# RSV.net
KiCad netlist of a schematic drawn in Altium Designer
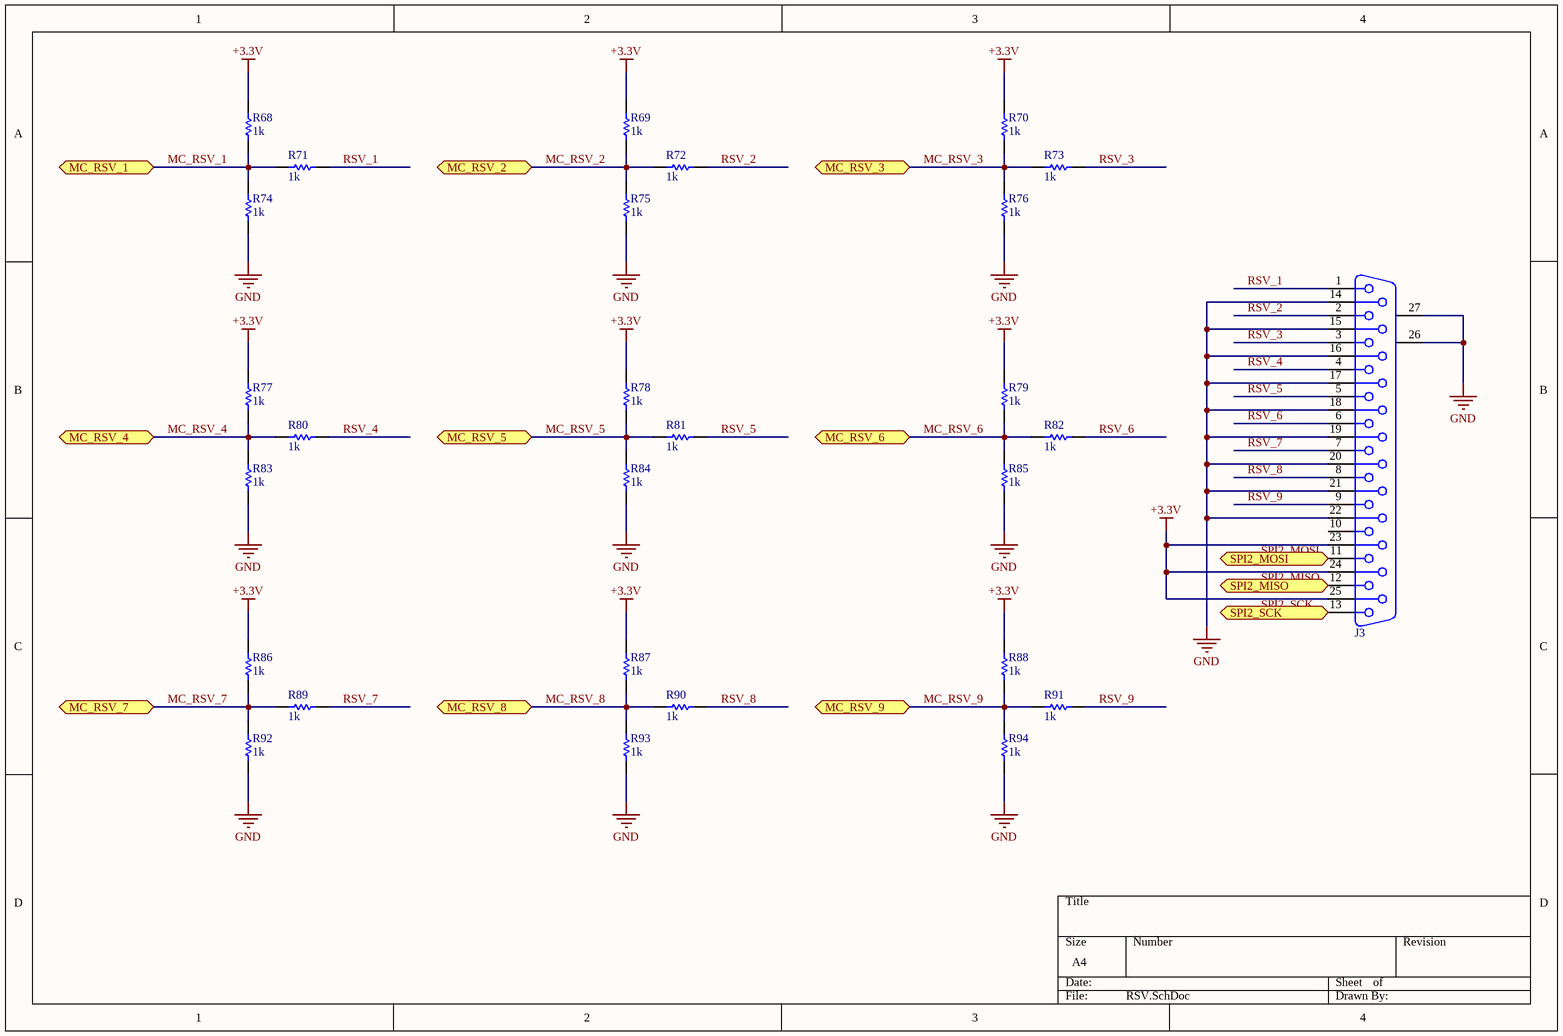
[diagram p0: RSV.SchDoc]

(export (version "E")
  (design (tool "Eeschema 10.0.6"))
  (components
    (comp (ref "J3")
      (value "DB25_Straight")
      (footprint "DB25_Straight")
      (description "Receptacle Assembly, 25 Position, Right Angle")
      (fields (field (name "PUBLISHER") "Altium Limited"))
      (libsource (lib "AfraLIB") (part "DB25_Straight"))
    )
    (comp (ref "R68")
      (value "1k")
      (footprint "R-805")
      (description "Resistor")
      (fields (field (name "Comment") "R-805"))
      (libsource (lib "AfraLIB") (part "R-805"))
    )
    (comp (ref "R69")
      (value "1k")
      (footprint "R-805")
      (description "Resistor")
      (fields (field (name "Comment") "R-805"))
      (libsource (lib "AfraLIB") (part "R-805"))
    )
    (comp (ref "R70")
      (value "1k")
      (footprint "R-805")
      (description "Resistor")
      (fields (field (name "Comment") "R-805"))
      (libsource (lib "AfraLIB") (part "R-805"))
    )
    (comp (ref "R71")
      (value "1k")
      (footprint "R-805")
      (description "Resistor")
      (fields (field (name "Comment") "R-805"))
      (libsource (lib "AfraLIB") (part "R-805"))
    )
    (comp (ref "R72")
      (value "1k")
      (footprint "R-805")
      (description "Resistor")
      (fields (field (name "Comment") "R-805"))
      (libsource (lib "AfraLIB") (part "R-805"))
    )
    (comp (ref "R73")
      (value "1k")
      (footprint "R-805")
      (description "Resistor")
      (fields (field (name "Comment") "R-805"))
      (libsource (lib "AfraLIB") (part "R-805"))
    )
    (comp (ref "R74")
      (value "1k")
      (footprint "R-805")
      (description "Resistor")
      (fields (field (name "Comment") "R-805"))
      (libsource (lib "AfraLIB") (part "R-805"))
    )
    (comp (ref "R75")
      (value "1k")
      (footprint "R-805")
      (description "Resistor")
      (fields (field (name "Comment") "R-805"))
      (libsource (lib "AfraLIB") (part "R-805"))
    )
    (comp (ref "R76")
      (value "1k")
      (footprint "R-805")
      (description "Resistor")
      (fields (field (name "Comment") "R-805"))
      (libsource (lib "AfraLIB") (part "R-805"))
    )
    (comp (ref "R77")
      (value "1k")
      (footprint "R-805")
      (description "Resistor")
      (fields (field (name "Comment") "R-805"))
      (libsource (lib "AfraLIB") (part "R-805"))
    )
    (comp (ref "R78")
      (value "1k")
      (footprint "R-805")
      (description "Resistor")
      (fields (field (name "Comment") "R-805"))
      (libsource (lib "AfraLIB") (part "R-805"))
    )
    (comp (ref "R79")
      (value "1k")
      (footprint "R-805")
      (description "Resistor")
      (fields (field (name "Comment") "R-805"))
      (libsource (lib "AfraLIB") (part "R-805"))
    )
    (comp (ref "R80")
      (value "1k")
      (footprint "R-805")
      (description "Resistor")
      (fields (field (name "Comment") "R-805"))
      (libsource (lib "AfraLIB") (part "R-805"))
    )
    (comp (ref "R81")
      (value "1k")
      (footprint "R-805")
      (description "Resistor")
      (fields (field (name "Comment") "R-805"))
      (libsource (lib "AfraLIB") (part "R-805"))
    )
    (comp (ref "R82")
      (value "1k")
      (footprint "R-805")
      (description "Resistor")
      (fields (field (name "Comment") "R-805"))
      (libsource (lib "AfraLIB") (part "R-805"))
    )
    (comp (ref "R83")
      (value "1k")
      (footprint "R-805")
      (description "Resistor")
      (fields (field (name "Comment") "R-805"))
      (libsource (lib "AfraLIB") (part "R-805"))
    )
    (comp (ref "R84")
      (value "1k")
      (footprint "R-805")
      (description "Resistor")
      (fields (field (name "Comment") "R-805"))
      (libsource (lib "AfraLIB") (part "R-805"))
    )
    (comp (ref "R85")
      (value "1k")
      (footprint "R-805")
      (description "Resistor")
      (fields (field (name "Comment") "R-805"))
      (libsource (lib "AfraLIB") (part "R-805"))
    )
    (comp (ref "R86")
      (value "1k")
      (footprint "R-805")
      (description "Resistor")
      (fields (field (name "Comment") "R-805"))
      (libsource (lib "AfraLIB") (part "R-805"))
    )
    (comp (ref "R87")
      (value "1k")
      (footprint "R-805")
      (description "Resistor")
      (fields (field (name "Comment") "R-805"))
      (libsource (lib "AfraLIB") (part "R-805"))
    )
    (comp (ref "R88")
      (value "1k")
      (footprint "R-805")
      (description "Resistor")
      (fields (field (name "Comment") "R-805"))
      (libsource (lib "AfraLIB") (part "R-805"))
    )
    (comp (ref "R89")
      (value "1k")
      (footprint "R-805")
      (description "Resistor")
      (fields (field (name "Comment") "R-805"))
      (libsource (lib "AfraLIB") (part "R-805"))
    )
    (comp (ref "R90")
      (value "1k")
      (footprint "R-805")
      (description "Resistor")
      (fields (field (name "Comment") "R-805"))
      (libsource (lib "AfraLIB") (part "R-805"))
    )
    (comp (ref "R91")
      (value "1k")
      (footprint "R-805")
      (description "Resistor")
      (fields (field (name "Comment") "R-805"))
      (libsource (lib "AfraLIB") (part "R-805"))
    )
    (comp (ref "R92")
      (value "1k")
      (footprint "R-805")
      (description "Resistor")
      (fields (field (name "Comment") "R-805"))
      (libsource (lib "AfraLIB") (part "R-805"))
    )
    (comp (ref "R93")
      (value "1k")
      (footprint "R-805")
      (description "Resistor")
      (fields (field (name "Comment") "R-805"))
      (libsource (lib "AfraLIB") (part "R-805"))
    )
    (comp (ref "R94")
      (value "1k")
      (footprint "R-805")
      (description "Resistor")
      (fields (field (name "Comment") "R-805"))
      (libsource (lib "AfraLIB") (part "R-805"))
    )
  )
  (nets
    (net (code "1") (name "+3.3V") (class "Default")
      (node (ref "J3") (pin "23") (pinfunction "23_23") (pintype "passive"))
      (node (ref "J3") (pin "24") (pinfunction "24_24") (pintype "passive"))
      (node (ref "J3") (pin "25") (pinfunction "25_25") (pintype "passive"))
      (node (ref "R68") (pin "2") (pinfunction "2_2") (pintype "passive"))
      (node (ref "R69") (pin "2") (pinfunction "2_2") (pintype "passive"))
      (node (ref "R70") (pin "2") (pinfunction "2_2") (pintype "passive"))
      (node (ref "R77") (pin "2") (pinfunction "2_2") (pintype "passive"))
      (node (ref "R78") (pin "2") (pinfunction "2_2") (pintype "passive"))
      (node (ref "R79") (pin "2") (pinfunction "2_2") (pintype "passive"))
      (node (ref "R86") (pin "2") (pinfunction "2_2") (pintype "passive"))
      (node (ref "R87") (pin "2") (pinfunction "2_2") (pintype "passive"))
      (node (ref "R88") (pin "2") (pinfunction "2_2") (pintype "passive"))
    )
    (net (code "2") (name "/MC_RSV_1") (class "Default")
      (node (ref "R68") (pin "1") (pinfunction "1_1") (pintype "passive"))
      (node (ref "R71") (pin "2") (pinfunction "2_2") (pintype "passive"))
      (node (ref "R74") (pin "2") (pinfunction "2_2") (pintype "passive"))
    )
    (net (code "3") (name "/MC_RSV_2") (class "Default")
      (node (ref "R69") (pin "1") (pinfunction "1_1") (pintype "passive"))
      (node (ref "R72") (pin "2") (pinfunction "2_2") (pintype "passive"))
      (node (ref "R75") (pin "2") (pinfunction "2_2") (pintype "passive"))
    )
    (net (code "4") (name "/MC_RSV_3") (class "Default")
      (node (ref "R70") (pin "1") (pinfunction "1_1") (pintype "passive"))
      (node (ref "R73") (pin "2") (pinfunction "2_2") (pintype "passive"))
      (node (ref "R76") (pin "2") (pinfunction "2_2") (pintype "passive"))
    )
    (net (code "5") (name "/MC_RSV_4") (class "Default")
      (node (ref "R77") (pin "1") (pinfunction "1_1") (pintype "passive"))
      (node (ref "R80") (pin "2") (pinfunction "2_2") (pintype "passive"))
      (node (ref "R83") (pin "2") (pinfunction "2_2") (pintype "passive"))
    )
    (net (code "6") (name "/MC_RSV_5") (class "Default")
      (node (ref "R78") (pin "1") (pinfunction "1_1") (pintype "passive"))
      (node (ref "R81") (pin "2") (pinfunction "2_2") (pintype "passive"))
      (node (ref "R84") (pin "2") (pinfunction "2_2") (pintype "passive"))
    )
    (net (code "7") (name "/MC_RSV_6") (class "Default")
      (node (ref "R79") (pin "1") (pinfunction "1_1") (pintype "passive"))
      (node (ref "R82") (pin "2") (pinfunction "2_2") (pintype "passive"))
      (node (ref "R85") (pin "2") (pinfunction "2_2") (pintype "passive"))
    )
    (net (code "8") (name "/MC_RSV_7") (class "Default")
      (node (ref "R86") (pin "1") (pinfunction "1_1") (pintype "passive"))
      (node (ref "R89") (pin "2") (pinfunction "2_2") (pintype "passive"))
      (node (ref "R92") (pin "2") (pinfunction "2_2") (pintype "passive"))
    )
    (net (code "9") (name "/MC_RSV_8") (class "Default")
      (node (ref "R87") (pin "1") (pinfunction "1_1") (pintype "passive"))
      (node (ref "R90") (pin "2") (pinfunction "2_2") (pintype "passive"))
      (node (ref "R93") (pin "2") (pinfunction "2_2") (pintype "passive"))
    )
    (net (code "10") (name "/MC_RSV_9") (class "Default")
      (node (ref "R88") (pin "1") (pinfunction "1_1") (pintype "passive"))
      (node (ref "R91") (pin "2") (pinfunction "2_2") (pintype "passive"))
      (node (ref "R94") (pin "2") (pinfunction "2_2") (pintype "passive"))
    )
    (net (code "11") (name "/RSV_1") (class "Default")
      (node (ref "J3") (pin "1") (pinfunction "1_1") (pintype "passive"))
      (node (ref "R71") (pin "1") (pinfunction "1_1") (pintype "passive"))
    )
    (net (code "12") (name "/RSV_2") (class "Default")
      (node (ref "J3") (pin "2") (pinfunction "2_2") (pintype "passive"))
      (node (ref "R72") (pin "1") (pinfunction "1_1") (pintype "passive"))
    )
    (net (code "13") (name "/RSV_3") (class "Default")
      (node (ref "J3") (pin "3") (pinfunction "3_3") (pintype "passive"))
      (node (ref "R73") (pin "1") (pinfunction "1_1") (pintype "passive"))
    )
    (net (code "14") (name "/RSV_4") (class "Default")
      (node (ref "J3") (pin "4") (pinfunction "4_4") (pintype "passive"))
      (node (ref "R80") (pin "1") (pinfunction "1_1") (pintype "passive"))
    )
    (net (code "15") (name "/RSV_5") (class "Default")
      (node (ref "J3") (pin "5") (pinfunction "5_5") (pintype "passive"))
      (node (ref "R81") (pin "1") (pinfunction "1_1") (pintype "passive"))
    )
    (net (code "16") (name "/RSV_6") (class "Default")
      (node (ref "J3") (pin "6") (pinfunction "6_6") (pintype "passive"))
      (node (ref "R82") (pin "1") (pinfunction "1_1") (pintype "passive"))
    )
    (net (code "17") (name "/RSV_7") (class "Default")
      (node (ref "J3") (pin "7") (pinfunction "7_7") (pintype "passive"))
      (node (ref "R89") (pin "1") (pinfunction "1_1") (pintype "passive"))
    )
    (net (code "18") (name "/RSV_8") (class "Default")
      (node (ref "J3") (pin "8") (pinfunction "8_8") (pintype "passive"))
      (node (ref "R90") (pin "1") (pinfunction "1_1") (pintype "passive"))
    )
    (net (code "19") (name "/RSV_9") (class "Default")
      (node (ref "J3") (pin "9") (pinfunction "9_9") (pintype "passive"))
      (node (ref "R91") (pin "1") (pinfunction "1_1") (pintype "passive"))
    )
    (net (code "20") (name "/SPI2_MISO") (class "Default")
      (node (ref "J3") (pin "12") (pinfunction "12_12") (pintype "passive"))
    )
    (net (code "21") (name "/SPI2_MOSI") (class "Default")
      (node (ref "J3") (pin "11") (pinfunction "11_11") (pintype "passive"))
    )
    (net (code "22") (name "/SPI2_SCK") (class "Default")
      (node (ref "J3") (pin "13") (pinfunction "13_13") (pintype "passive"))
    )
    (net (code "23") (name "GND") (class "Default")
      (node (ref "J3") (pin "14") (pinfunction "14_14") (pintype "passive"))
      (node (ref "J3") (pin "15") (pinfunction "15_15") (pintype "passive"))
      (node (ref "J3") (pin "16") (pinfunction "16_16") (pintype "passive"))
      (node (ref "J3") (pin "17") (pinfunction "17_17") (pintype "passive"))
      (node (ref "J3") (pin "18") (pinfunction "18_18") (pintype "passive"))
      (node (ref "J3") (pin "19") (pinfunction "19_19") (pintype "passive"))
      (node (ref "J3") (pin "20") (pinfunction "20_20") (pintype "passive"))
      (node (ref "J3") (pin "21") (pinfunction "21_21") (pintype "passive"))
      (node (ref "J3") (pin "22") (pinfunction "22_22") (pintype "passive"))
      (node (ref "J3") (pin "26") (pinfunction "MH1_26") (pintype "passive"))
      (node (ref "J3") (pin "27") (pinfunction "MH2_27") (pintype "passive"))
      (node (ref "R74") (pin "1") (pinfunction "1_1") (pintype "passive"))
      (node (ref "R75") (pin "1") (pinfunction "1_1") (pintype "passive"))
      (node (ref "R76") (pin "1") (pinfunction "1_1") (pintype "passive"))
      (node (ref "R83") (pin "1") (pinfunction "1_1") (pintype "passive"))
      (node (ref "R84") (pin "1") (pinfunction "1_1") (pintype "passive"))
      (node (ref "R85") (pin "1") (pinfunction "1_1") (pintype "passive"))
      (node (ref "R92") (pin "1") (pinfunction "1_1") (pintype "passive"))
      (node (ref "R93") (pin "1") (pinfunction "1_1") (pintype "passive"))
      (node (ref "R94") (pin "1") (pinfunction "1_1") (pintype "passive"))
    )
    (net (code "24") (name "unconnected-(J3-Pad10)") (class "Default")
      (node (ref "J3") (pin "10") (pinfunction "10_10") (pintype "passive"))
    )
  )
)
